# mush_indi_gnat.net
KiCad netlist of a schematic drawn in EAGLE
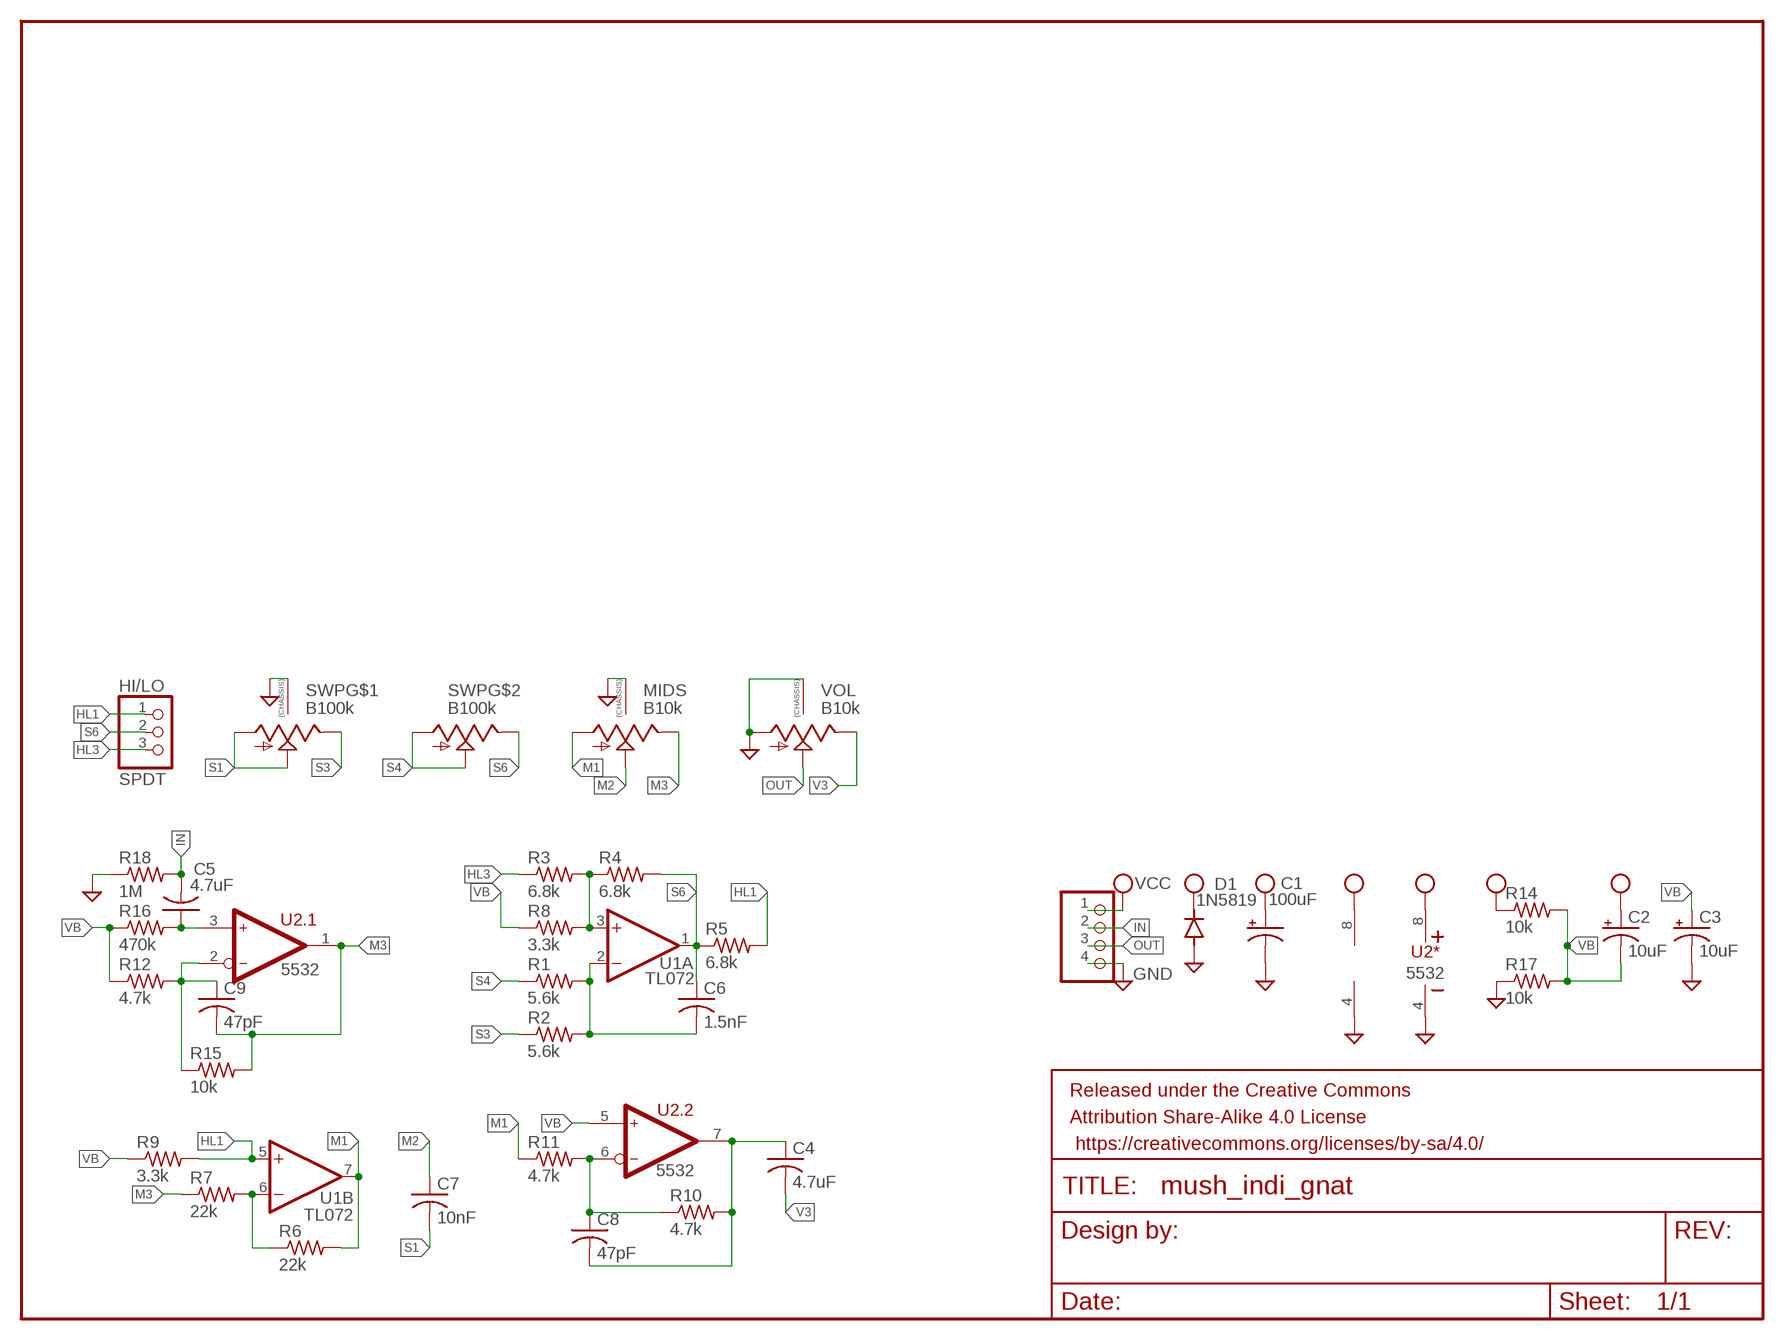
[diagram p0: schematic, sheet 1]

(export (version "E")
  (design (tool "Eeschema 10.0.6"))
  (components
    (comp (ref "C1")
      (value "100uF")
      (footprint "eagle-import:PAN_B_SMD+THRU")
      (libsource (lib "eagle-import") (part "CAP_SMD+THRUPAN_B"))
    )
    (comp (ref "C2")
      (value "10uF")
      (footprint "eagle-import:CAPMP3216X180N")
      (libsource (lib "eagle-import") (part "C-POL-USTANTALUM-1206(3216-METRIC)_"))
    )
    (comp (ref "C3")
      (value "10uF")
      (footprint "eagle-import:CAPMP3216X180N")
      (libsource (lib "eagle-import") (part "C-POL-USTANTALUM-1206(3216-METRIC)_"))
    )
    (comp (ref "C4")
      (value "4.7uF")
      (footprint "eagle-import:C0805")
      (libsource (lib "eagle-import") (part "C-USC0805"))
    )
    (comp (ref "C5")
      (value "4.7uF")
      (footprint "eagle-import:C0805")
      (libsource (lib "eagle-import") (part "C-USC0805"))
    )
    (comp (ref "C6")
      (value "1.5nF")
      (footprint "eagle-import:C0603")
      (libsource (lib "eagle-import") (part "C-USC0603"))
    )
    (comp (ref "C7")
      (value "10nF")
      (footprint "eagle-import:C0603")
      (libsource (lib "eagle-import") (part "C-USC0603"))
    )
    (comp (ref "C8")
      (value "47pF")
      (footprint "eagle-import:C0603")
      (libsource (lib "eagle-import") (part "C-USC0603"))
    )
    (comp (ref "C9")
      (value "47pF")
      (footprint "eagle-import:C0603")
      (libsource (lib "eagle-import") (part "C-USC0603"))
    )
    (comp (ref "D1")
      (value "1N5819")
      (footprint "eagle-import:SOD123")
      (libsource (lib "eagle-import") (part "DIODE-SOD123"))
    )
    (comp (ref "FRAME1")
      (value "FRAME-LETTERNO_PACKAGE")
      (footprint "eagle-import:DUMMY")
      (fields (field (name "DESIGNER") "Nobody"))
      (libsource (lib "eagle-import") (part "FRAME-LETTERNO_PACKAGE"))
    )
    (comp (ref "HI/LO")
      (value "SPDT")
      (footprint "eagle-import:1X03")
      (libsource (lib "eagle-import") (part "PINHD-1X3"))
    )
    (comp (ref "JP1")
      (value "PINHD-1X4")
      (footprint "eagle-import:1X04")
      (libsource (lib "eagle-import") (part "PINHD-1X4"))
    )
    (comp (ref "MIDS")
      (value "B10k")
      (footprint "eagle-import:9MM_SNAP-IN_POT")
      (libsource (lib "eagle-import") (part "9MM_SNAP-IN_POT_CHASSIS"))
    )
    (comp (ref "R1")
      (value "5.6k")
      (footprint "eagle-import:R0603")
      (libsource (lib "eagle-import") (part "R-US_R0603"))
    )
    (comp (ref "R2")
      (value "5.6k")
      (footprint "eagle-import:R0603")
      (libsource (lib "eagle-import") (part "R-US_R0603"))
    )
    (comp (ref "R3")
      (value "6.8k")
      (footprint "eagle-import:R0603")
      (libsource (lib "eagle-import") (part "R-US_R0603"))
    )
    (comp (ref "R4")
      (value "6.8k")
      (footprint "eagle-import:R0603")
      (libsource (lib "eagle-import") (part "R-US_R0603"))
    )
    (comp (ref "R5")
      (value "6.8k")
      (footprint "eagle-import:R0603")
      (libsource (lib "eagle-import") (part "R-US_R0603"))
    )
    (comp (ref "R6")
      (value "22k")
      (footprint "eagle-import:R0603")
      (libsource (lib "eagle-import") (part "R-US_R0603"))
    )
    (comp (ref "R7")
      (value "22k")
      (footprint "eagle-import:R0603")
      (libsource (lib "eagle-import") (part "R-US_R0603"))
    )
    (comp (ref "R8")
      (value "3.3k")
      (footprint "eagle-import:R0603")
      (libsource (lib "eagle-import") (part "R-US_R0603"))
    )
    (comp (ref "R9")
      (value "3.3k")
      (footprint "eagle-import:R0603")
      (libsource (lib "eagle-import") (part "R-US_R0603"))
    )
    (comp (ref "R10")
      (value "4.7k")
      (footprint "eagle-import:R0603")
      (libsource (lib "eagle-import") (part "R-US_R0603"))
    )
    (comp (ref "R11")
      (value "4.7k")
      (footprint "eagle-import:R0603")
      (libsource (lib "eagle-import") (part "R-US_R0603"))
    )
    (comp (ref "R12")
      (value "4.7k")
      (footprint "eagle-import:R0603")
      (libsource (lib "eagle-import") (part "R-US_R0603"))
    )
    (comp (ref "R14")
      (value "10k")
      (footprint "eagle-import:R0603")
      (libsource (lib "eagle-import") (part "R-US_R0603"))
    )
    (comp (ref "R15")
      (value "10k")
      (footprint "eagle-import:R0603")
      (libsource (lib "eagle-import") (part "R-US_R0603"))
    )
    (comp (ref "R16")
      (value "470k")
      (footprint "eagle-import:R0603")
      (libsource (lib "eagle-import") (part "R-US_R0603"))
    )
    (comp (ref "R17")
      (value "10k")
      (footprint "eagle-import:R0603")
      (libsource (lib "eagle-import") (part "R-US_R0603"))
    )
    (comp (ref "R18")
      (value "1M")
      (footprint "eagle-import:R0603")
      (libsource (lib "eagle-import") (part "R-US_R0603"))
    )
    (comp (ref "SWP")
      (value "B100k")
      (footprint "eagle-import:DUAL_9MM_SNAP-IN_POT")
      (libsource (lib "eagle-import") (part "ALPHA-9MM-DUALPOT"))
    )
    (comp (ref "U1")
      (value "TL072")
      (footprint "eagle-import:TSSOP-8")
      (libsource (lib "eagle-import") (part "TL072TSSOP"))
    )
    (comp (ref "U2")
      (value "5532")
      (footprint "eagle-import:SO-8")
      (libsource (lib "eagle-import") (part "NJM5532M"))
    )
    (comp (ref "VOL")
      (value "B10k")
      (footprint "eagle-import:9MM_SNAP-IN_POT")
      (libsource (lib "eagle-import") (part "9MM_SNAP-IN_POT_CHASSIS"))
    )
  )
  (nets
    (net (code "1") (name "GND") (class "Default")
      (node (ref "C1") (pin "-") (pinfunction "-_-") (pintype "passive"))
      (node (ref "C1") (pin "--") (pinfunction "-_--") (pintype "passive"))
      (node (ref "C3") (pin "2") (pinfunction "-_2") (pintype "passive"))
      (node (ref "D1") (pin "A") (pinfunction "A_A") (pintype "passive"))
      (node (ref "JP1") (pin "4") (pinfunction "4_4") (pintype "passive"))
      (node (ref "MIDS") (pin "CHASSIS1") (pinfunction "P$1_CHASSIS1") (pintype "passive"))
      (node (ref "MIDS") (pin "CHASSIS2") (pinfunction "P$1_CHASSIS2") (pintype "passive"))
      (node (ref "R17") (pin "1") (pinfunction "1_1") (pintype "passive"))
      (node (ref "R18") (pin "1") (pinfunction "1_1") (pintype "passive"))
      (node (ref "SWP") (pin "CHASSIS1") (pinfunction "P$1_CHASSIS1") (pintype "passive"))
      (node (ref "SWP") (pin "CHASSIS2") (pinfunction "P$1_CHASSIS2") (pintype "passive"))
      (node (ref "U1") (pin "4") (pinfunction "V-_4") (pintype "power_in"))
      (node (ref "U2") (pin "4") (pinfunction "V-_4") (pintype "power_in"))
      (node (ref "VOL") (pin "1") (pinfunction "A_1") (pintype "passive"))
      (node (ref "VOL") (pin "CHASSIS1") (pinfunction "P$1_CHASSIS1") (pintype "passive"))
      (node (ref "VOL") (pin "CHASSIS2") (pinfunction "P$1_CHASSIS2") (pintype "passive"))
    )
    (net (code "2") (name "HL1") (class "Default")
      (node (ref "HI/LO") (pin "1") (pinfunction "1_1") (pintype "passive"))
      (node (ref "R5") (pin "2") (pinfunction "2_2") (pintype "passive"))
      (node (ref "R9") (pin "2") (pinfunction "2_2") (pintype "passive"))
      (node (ref "U1") (pin "5") (pinfunction "+IN_5") (pintype "input"))
    )
    (net (code "3") (name "HL3") (class "Default")
      (node (ref "HI/LO") (pin "3") (pinfunction "3_3") (pintype "passive"))
      (node (ref "R3") (pin "1") (pinfunction "1_1") (pintype "passive"))
    )
    (net (code "4") (name "IN") (class "Default")
      (node (ref "C5") (pin "2") (pinfunction "2_2") (pintype "passive"))
      (node (ref "JP1") (pin "2") (pinfunction "2_2") (pintype "passive"))
      (node (ref "R18") (pin "2") (pinfunction "2_2") (pintype "passive"))
    )
    (net (code "5") (name "M1") (class "Default")
      (node (ref "MIDS") (pin "1") (pinfunction "A_1") (pintype "passive"))
      (node (ref "R11") (pin "1") (pinfunction "1_1") (pintype "passive"))
      (node (ref "R6") (pin "2") (pinfunction "2_2") (pintype "passive"))
      (node (ref "U1") (pin "7") (pinfunction "OUT_7") (pintype "output"))
    )
    (net (code "6") (name "M2") (class "Default")
      (node (ref "C7") (pin "1") (pinfunction "1_1") (pintype "passive"))
      (node (ref "MIDS") (pin "2") (pinfunction "S_2") (pintype "passive"))
    )
    (net (code "7") (name "M3") (class "Default")
      (node (ref "C9") (pin "2") (pinfunction "2_2") (pintype "passive"))
      (node (ref "MIDS") (pin "3") (pinfunction "E_3") (pintype "passive"))
      (node (ref "R15") (pin "2") (pinfunction "2_2") (pintype "passive"))
      (node (ref "R7") (pin "1") (pinfunction "1_1") (pintype "passive"))
      (node (ref "U2") (pin "1") (pinfunction "OUT_1") (pintype "output"))
    )
    (net (code "8") (name "Net-(U1A-+IN)") (class "Default")
      (node (ref "R3") (pin "2") (pinfunction "2_2") (pintype "passive"))
      (node (ref "R4") (pin "1") (pinfunction "1_1") (pintype "passive"))
      (node (ref "R8") (pin "2") (pinfunction "2_2") (pintype "passive"))
      (node (ref "U1") (pin "3") (pinfunction "+IN_3") (pintype "input"))
    )
    (net (code "9") (name "Net-(U1A--IN)") (class "Default")
      (node (ref "C6") (pin "2") (pinfunction "2_2") (pintype "passive"))
      (node (ref "R1") (pin "2") (pinfunction "2_2") (pintype "passive"))
      (node (ref "R2") (pin "2") (pinfunction "2_2") (pintype "passive"))
      (node (ref "U1") (pin "2") (pinfunction "-IN_2") (pintype "input"))
    )
    (net (code "10") (name "Net-(U1B--IN)") (class "Default")
      (node (ref "R6") (pin "1") (pinfunction "1_1") (pintype "passive"))
      (node (ref "R7") (pin "2") (pinfunction "2_2") (pintype "passive"))
      (node (ref "U1") (pin "6") (pinfunction "-IN_6") (pintype "input"))
    )
    (net (code "11") (name "Net-(U2B-IN+)") (class "Default")
      (node (ref "C5") (pin "1") (pinfunction "1_1") (pintype "passive"))
      (node (ref "R16") (pin "2") (pinfunction "2_2") (pintype "passive"))
      (node (ref "U2") (pin "3") (pinfunction "IN+_3") (pintype "input"))
    )
    (net (code "12") (name "Net-(U2B-IN-)") (class "Default")
      (node (ref "C9") (pin "1") (pinfunction "1_1") (pintype "passive"))
      (node (ref "R12") (pin "2") (pinfunction "2_2") (pintype "passive"))
      (node (ref "R15") (pin "1") (pinfunction "1_1") (pintype "passive"))
      (node (ref "U2") (pin "2") (pinfunction "IN-_2") (pintype "input"))
    )
    (net (code "13") (name "Net-(U2C-IN-)") (class "Default")
      (node (ref "C8") (pin "1") (pinfunction "1_1") (pintype "passive"))
      (node (ref "R10") (pin "1") (pinfunction "1_1") (pintype "passive"))
      (node (ref "R11") (pin "2") (pinfunction "2_2") (pintype "passive"))
      (node (ref "U2") (pin "6") (pinfunction "IN-_6") (pintype "input"))
    )
    (net (code "14") (name "Net-(U2C-OUT)") (class "Default")
      (node (ref "C4") (pin "1") (pinfunction "1_1") (pintype "passive"))
      (node (ref "C8") (pin "2") (pinfunction "2_2") (pintype "passive"))
      (node (ref "R10") (pin "2") (pinfunction "2_2") (pintype "passive"))
      (node (ref "U2") (pin "7") (pinfunction "OUT_7") (pintype "output"))
    )
    (net (code "15") (name "OUT") (class "Default")
      (node (ref "JP1") (pin "3") (pinfunction "3_3") (pintype "passive"))
      (node (ref "VOL") (pin "2") (pinfunction "S_2") (pintype "passive"))
    )
    (net (code "16") (name "S1") (class "Default")
      (node (ref "C7") (pin "2") (pinfunction "2_2") (pintype "passive"))
      (node (ref "SWP") (pin "1") (pinfunction "A_1") (pintype "passive"))
      (node (ref "SWP") (pin "2") (pinfunction "S_2") (pintype "passive"))
    )
    (net (code "17") (name "S3") (class "Default")
      (node (ref "R2") (pin "1") (pinfunction "1_1") (pintype "passive"))
      (node (ref "SWP") (pin "3") (pinfunction "E_3") (pintype "passive"))
    )
    (net (code "18") (name "S4") (class "Default")
      (node (ref "R1") (pin "1") (pinfunction "1_1") (pintype "passive"))
      (node (ref "SWP") (pin "1B") (pinfunction "A_1B") (pintype "passive"))
      (node (ref "SWP") (pin "2B") (pinfunction "S_2B") (pintype "passive"))
    )
    (net (code "19") (name "S6") (class "Default")
      (node (ref "C6") (pin "1") (pinfunction "1_1") (pintype "passive"))
      (node (ref "HI/LO") (pin "2") (pinfunction "2_2") (pintype "passive"))
      (node (ref "R4") (pin "2") (pinfunction "2_2") (pintype "passive"))
      (node (ref "R5") (pin "1") (pinfunction "1_1") (pintype "passive"))
      (node (ref "SWP") (pin "3B") (pinfunction "E_3B") (pintype "passive"))
      (node (ref "U1") (pin "1") (pinfunction "OUT_1") (pintype "output"))
    )
    (net (code "20") (name "V3") (class "Default")
      (node (ref "C4") (pin "2") (pinfunction "2_2") (pintype "passive"))
      (node (ref "VOL") (pin "3") (pinfunction "E_3") (pintype "passive"))
    )
    (net (code "21") (name "VB") (class "Default")
      (node (ref "C2") (pin "2") (pinfunction "-_2") (pintype "passive"))
      (node (ref "C3") (pin "1") (pinfunction "+_1") (pintype "passive"))
      (node (ref "R12") (pin "1") (pinfunction "1_1") (pintype "passive"))
      (node (ref "R14") (pin "2") (pinfunction "2_2") (pintype "passive"))
      (node (ref "R16") (pin "1") (pinfunction "1_1") (pintype "passive"))
      (node (ref "R17") (pin "2") (pinfunction "2_2") (pintype "passive"))
      (node (ref "R8") (pin "1") (pinfunction "1_1") (pintype "passive"))
      (node (ref "R9") (pin "1") (pinfunction "1_1") (pintype "passive"))
      (node (ref "U2") (pin "5") (pinfunction "IN+_5") (pintype "input"))
    )
    (net (code "22") (name "VCC") (class "Default")
      (node (ref "C1") (pin "+") (pinfunction "+_+") (pintype "passive"))
      (node (ref "C1") (pin "++") (pinfunction "+_++") (pintype "passive"))
      (node (ref "C2") (pin "1") (pinfunction "+_1") (pintype "passive"))
      (node (ref "D1") (pin "C") (pinfunction "C_C") (pintype "passive"))
      (node (ref "JP1") (pin "1") (pinfunction "1_1") (pintype "passive"))
      (node (ref "R14") (pin "1") (pinfunction "1_1") (pintype "passive"))
      (node (ref "U1") (pin "8") (pinfunction "V+_8") (pintype "power_in"))
      (node (ref "U2") (pin "8") (pinfunction "V+_8") (pintype "power_in"))
    )
  )
)
